# ulchich.net
KiCad netlist of a schematic drawn in Altium Designer
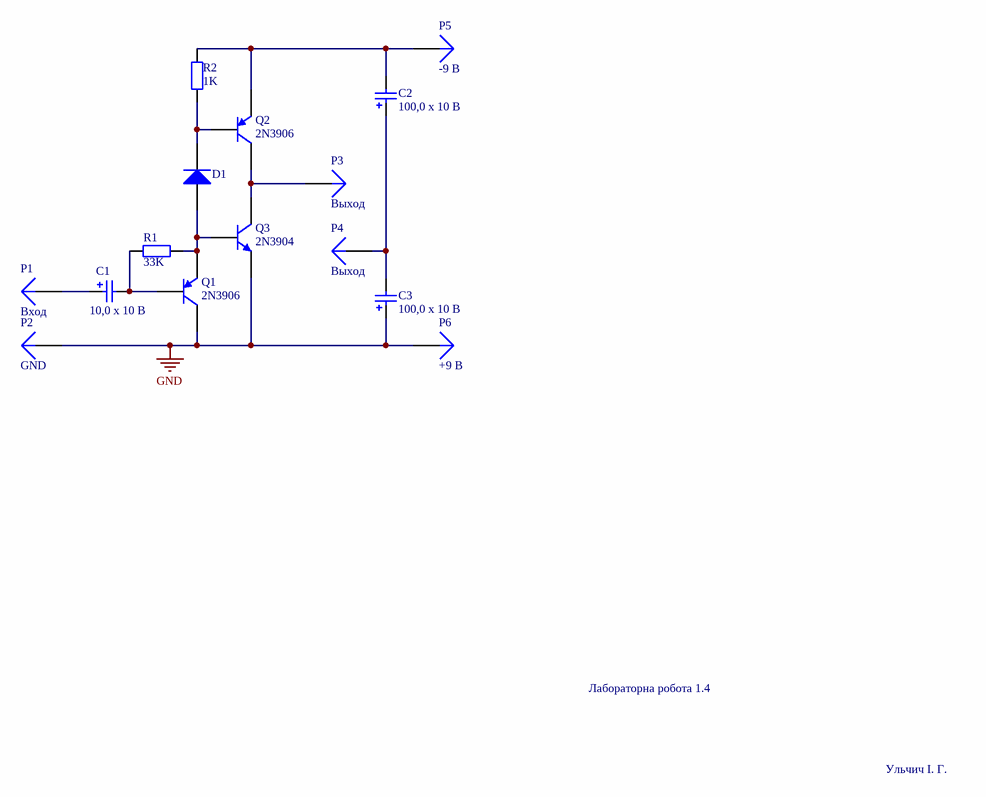
[diagram p0: ulchich.SchDoc]

(export (version "E")
  (design (tool "Eeschema 10.0.6"))
  (components
    (comp (ref "C1")
      (value "10,0 x 10 В")
      (footprint "POLAR0.8")
      (description "Polarized Capacitor (Axial)")
      (fields (field (name "Comment") "Cap Pol2") (field (name "PUBLISHER") "Altium Limited"))
      (libsource (lib "Miscellaneous Devices") (part "Cap Pol2"))
    )
    (comp (ref "C2")
      (value "100,0 x 10 В")
      (footprint "POLAR0.8")
      (description "Polarized Capacitor (Axial)")
      (fields (field (name "Comment") "Cap Pol2") (field (name "PUBLISHER") "Altium Limited"))
      (libsource (lib "Miscellaneous Devices") (part "Cap Pol2"))
    )
    (comp (ref "C3")
      (value "100,0 x 10 В")
      (footprint "POLAR0.8")
      (description "Polarized Capacitor (Axial)")
      (fields (field (name "Comment") "Cap Pol2") (field (name "PUBLISHER") "Altium Limited"))
      (libsource (lib "Miscellaneous Devices") (part "Cap Pol2"))
    )
    (comp (ref "D1")
      (value "Diode 1N4148")
      (footprint "DO-35")
      (description "High Conductance Fast Diode")
      (fields (field (name "PUBLISHER") "Altium Limited"))
      (libsource (lib "Miscellaneous Devices") (part "Diode 1N4148"))
    )
    (comp (ref "P1")
      (value "Вход")
      (footprint "PIN1")
      (description "Plug")
      (fields (field (name "PUBLISHER") "Altium Limited"))
      (libsource (lib "Miscellaneous Connectors") (part "Plug"))
    )
    (comp (ref "P2")
      (value "GND")
      (footprint "PIN1")
      (description "Plug")
      (fields (field (name "PUBLISHER") "Altium Limited"))
      (libsource (lib "Miscellaneous Connectors") (part "Plug"))
    )
    (comp (ref "P3")
      (value "Выход")
      (footprint "PIN1")
      (description "Plug")
      (fields (field (name "PUBLISHER") "Altium Limited"))
      (libsource (lib "Miscellaneous Connectors") (part "Plug"))
    )
    (comp (ref "P4")
      (value "Выход")
      (footprint "PIN1")
      (description "Plug")
      (fields (field (name "PUBLISHER") "Altium Limited"))
      (libsource (lib "Miscellaneous Connectors") (part "Plug"))
    )
    (comp (ref "P5")
      (value "-9 В")
      (footprint "PIN1")
      (description "Plug")
      (fields (field (name "PUBLISHER") "Altium Limited"))
      (libsource (lib "Miscellaneous Connectors") (part "Plug"))
    )
    (comp (ref "P6")
      (value "+9 В")
      (footprint "PIN1")
      (description "Plug")
      (fields (field (name "PUBLISHER") "Altium Limited"))
      (libsource (lib "Miscellaneous Connectors") (part "Plug"))
    )
    (comp (ref "Q1")
      (value "2N3906")
      (footprint "TO-92A")
      (description "PNP General Purpose Amplifier")
      (fields (field (name "PUBLISHER") "Altium Limited"))
      (libsource (lib "Miscellaneous Devices") (part "2N3906"))
    )
    (comp (ref "Q2")
      (value "2N3906")
      (footprint "TO-92A")
      (description "PNP General Purpose Amplifier")
      (fields (field (name "PUBLISHER") "Altium Limited"))
      (libsource (lib "Miscellaneous Devices") (part "2N3906"))
    )
    (comp (ref "Q3")
      (value "2N3904")
      (footprint "TO-92A")
      (description "NPN General Purpose Amplifier")
      (fields (field (name "PUBLISHER") "Altium Limited"))
      (libsource (lib "Miscellaneous Devices") (part "2N3904"))
    )
    (comp (ref "R1")
      (value "33K")
      (footprint "AXIAL-0.4")
      (description "Resistor")
      (fields (field (name "Comment") "Res2") (field (name "PUBLISHER") "Altium Limited"))
      (libsource (lib "") (part "Res2_1"))
    )
    (comp (ref "R2")
      (value "1K")
      (footprint "AXIAL-0.4")
      (description "Resistor")
      (fields (field (name "Comment") "Res2") (field (name "PUBLISHER") "Altium Limited"))
      (libsource (lib "Miscellaneous Devices") (part "Res2"))
    )
  )
  (nets
    (net (code "1") (name "GND") (class "Default")
      (node (ref "C3") (pin "1") (pinfunction "1_1") (pintype "passive"))
      (node (ref "P2") (pin "1") (pinfunction "1_1") (pintype "passive"))
      (node (ref "P6") (pin "1") (pinfunction "1_1") (pintype "passive"))
      (node (ref "Q1") (pin "3") (pinfunction "C_3") (pintype "passive"))
      (node (ref "Q3") (pin "1") (pinfunction "E_1") (pintype "passive"))
    )
    (net (code "2") (name "Net-(C1-Pad1)") (class "Default")
      (node (ref "C1") (pin "1") (pinfunction "1_1") (pintype "passive"))
      (node (ref "P1") (pin "1") (pinfunction "1_1") (pintype "passive"))
    )
    (net (code "3") (name "Net-(C2-Pad1)") (class "Default")
      (node (ref "C2") (pin "1") (pinfunction "1_1") (pintype "passive"))
      (node (ref "C3") (pin "2") (pinfunction "2_2") (pintype "passive"))
      (node (ref "P4") (pin "1") (pinfunction "1_1") (pintype "passive"))
    )
    (net (code "4") (name "Net-(D1-A)") (class "Default")
      (node (ref "D1") (pin "1") (pinfunction "A_1") (pintype "passive"))
      (node (ref "Q1") (pin "1") (pinfunction "E_1") (pintype "passive"))
      (node (ref "Q3") (pin "2") (pinfunction "B_2") (pintype "passive"))
      (node (ref "R1") (pin "2") (pinfunction "2_2") (pintype "passive"))
    )
    (net (code "5") (name "Net-(D1-K)") (class "Default")
      (node (ref "D1") (pin "2") (pinfunction "K_2") (pintype "passive"))
      (node (ref "Q2") (pin "2") (pinfunction "B_2") (pintype "passive"))
      (node (ref "R2") (pin "1") (pinfunction "1_1") (pintype "passive"))
    )
    (net (code "6") (name "Net-(Q1-B)") (class "Default")
      (node (ref "C1") (pin "2") (pinfunction "2_2") (pintype "passive"))
      (node (ref "Q1") (pin "2") (pinfunction "B_2") (pintype "passive"))
      (node (ref "R1") (pin "1") (pinfunction "1_1") (pintype "passive"))
    )
    (net (code "7") (name "Net-(Q2-C)") (class "Default")
      (node (ref "P3") (pin "1") (pinfunction "1_1") (pintype "passive"))
      (node (ref "Q2") (pin "3") (pinfunction "C_3") (pintype "passive"))
      (node (ref "Q3") (pin "3") (pinfunction "C_3") (pintype "passive"))
    )
    (net (code "8") (name "Net-(Q2-E)") (class "Default")
      (node (ref "C2") (pin "2") (pinfunction "2_2") (pintype "passive"))
      (node (ref "P5") (pin "1") (pinfunction "1_1") (pintype "passive"))
      (node (ref "Q2") (pin "1") (pinfunction "E_1") (pintype "passive"))
      (node (ref "R2") (pin "2") (pinfunction "2_2") (pintype "passive"))
    )
  )
)
